# design.net
KiCad netlist of a schematic drawn in Altium Designer
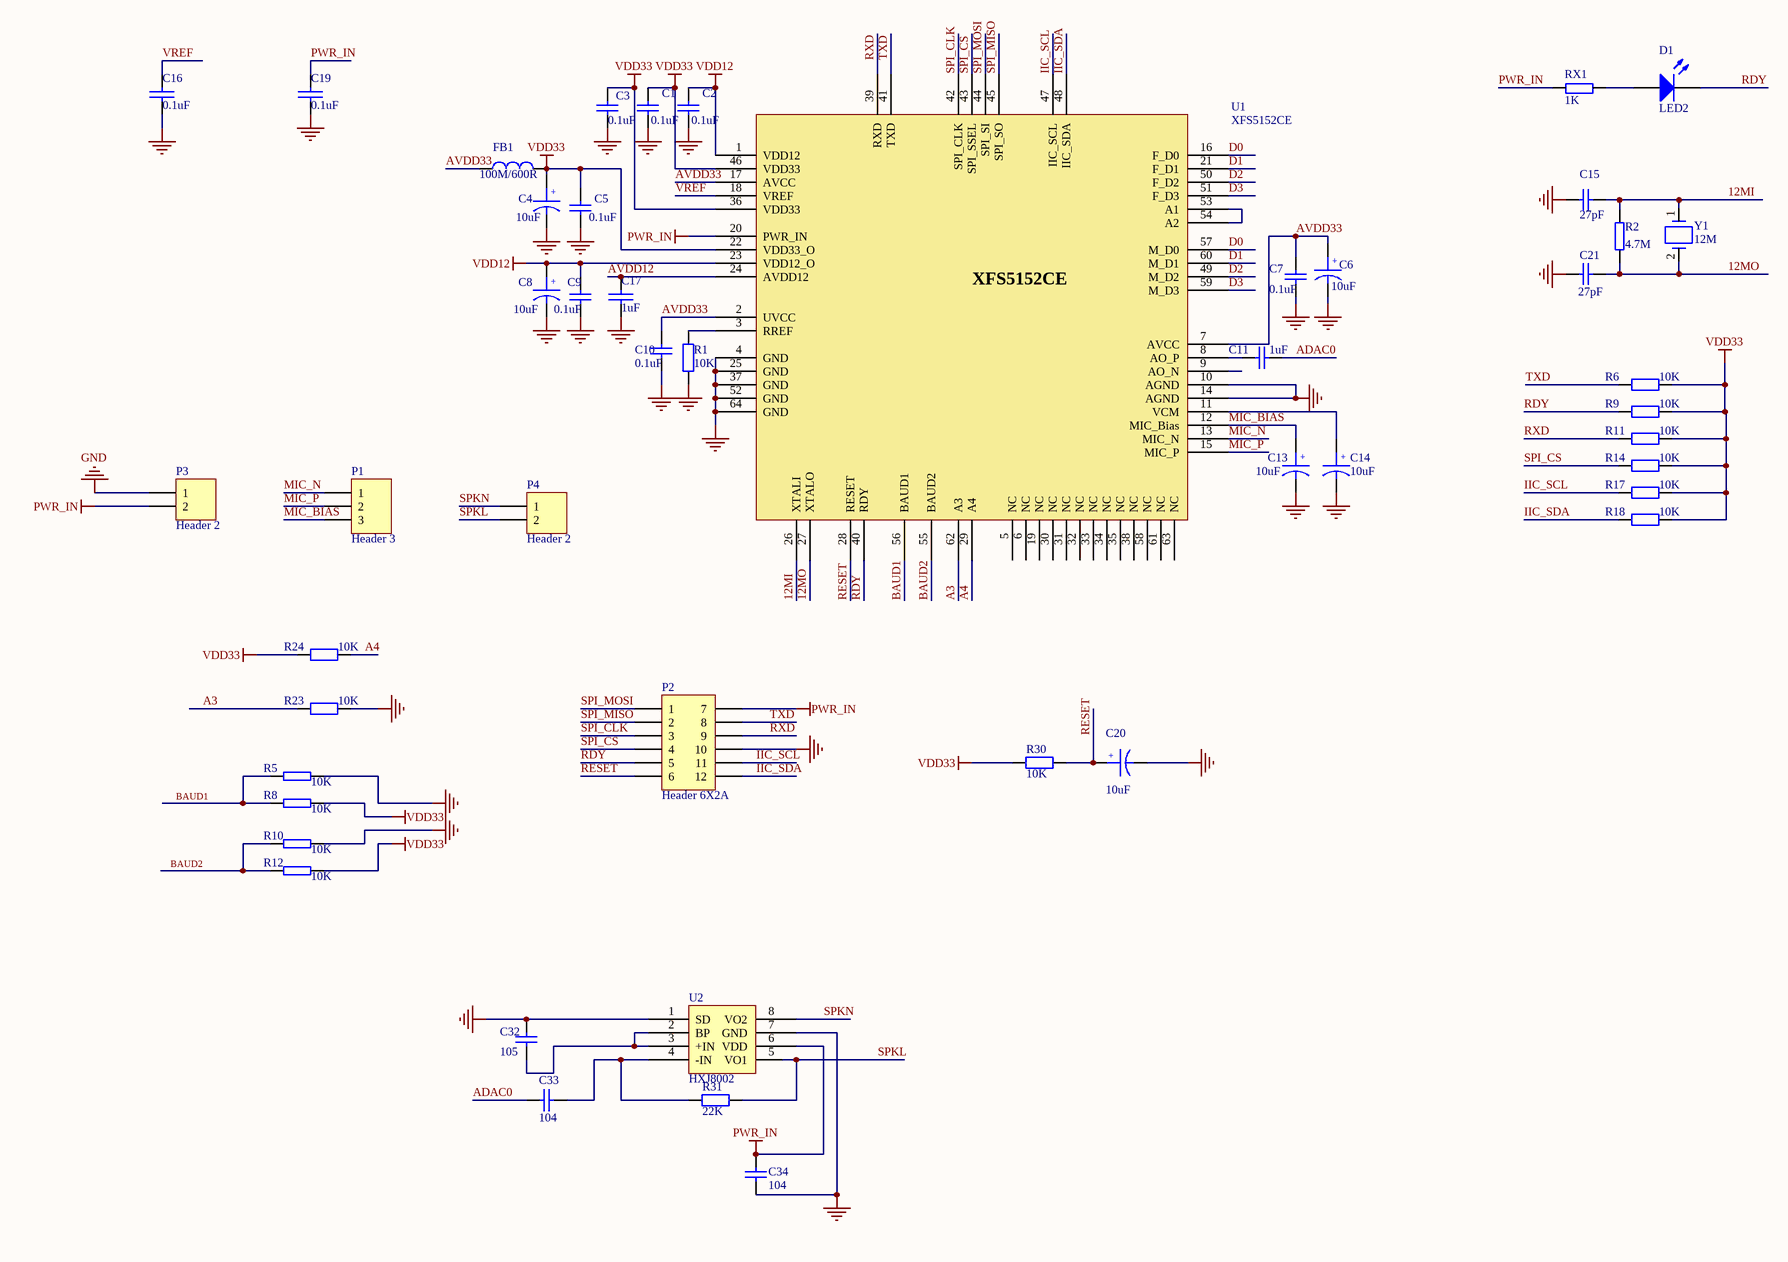
[diagram p0: 日原理图.SchDoc]

(export (version "E")
  (design (tool "Eeschema 10.0.6"))
  (components
    (comp (ref "C1")
      (value "0.1uF")
      (footprint "0603P")
      (description "电容")
      (fields (field (name "PUBLISHER") "Altium Limited"))
      (libsource (lib "*") (part "Cap NP"))
    )
    (comp (ref "C2")
      (value "0.1uF")
      (footprint "0603P")
      (description "电容")
      (fields (field (name "PUBLISHER") "Altium Limited"))
      (libsource (lib "*") (part "Cap NP"))
    )
    (comp (ref "C3")
      (value "0.1uF")
      (footprint "0603P")
      (description "电容")
      (fields (field (name "PUBLISHER") "Altium Limited"))
      (libsource (lib "*") (part "Cap NP"))
    )
    (comp (ref "C4") (value "10uF") (footprint "0805") (libsource (lib "*") (part "CAP POL")))
    (comp (ref "C5")
      (value "0.1uF")
      (footprint "0603P")
      (description "电容")
      (fields (field (name "PUBLISHER") "Altium Limited"))
      (libsource (lib "*") (part "Cap NP"))
    )
    (comp (ref "C6") (value "10uF") (footprint "0805") (libsource (lib "*") (part "CAP POL")))
    (comp (ref "C7")
      (value "0.1uF")
      (footprint "0603P")
      (description "电容")
      (fields (field (name "PUBLISHER") "Altium Limited"))
      (libsource (lib "*") (part "Cap NP"))
    )
    (comp (ref "C8") (value "10uF") (footprint "0805") (libsource (lib "*") (part "CAP POL")))
    (comp (ref "C9")
      (value "0.1uF")
      (footprint "0603P")
      (description "电容")
      (fields (field (name "PUBLISHER") "Altium Limited"))
      (libsource (lib "*") (part "Cap NP"))
    )
    (comp (ref "C10")
      (value "0.1uF")
      (footprint "0603P")
      (description "电容")
      (fields (field (name "PUBLISHER") "Altium Limited"))
      (libsource (lib "*") (part "Cap NP"))
    )
    (comp (ref "C11")
      (value "1uF")
      (footprint "0603P")
      (description "电容")
      (fields (field (name "PUBLISHER") "Altium Limited"))
      (libsource (lib "*") (part "Cap NP"))
    )
    (comp (ref "C13") (value "10uF") (footprint "0805") (libsource (lib "*") (part "CAP POL")))
    (comp (ref "C14") (value "10uF") (footprint "0805") (libsource (lib "*") (part "CAP POL")))
    (comp (ref "C15")
      (value "27pF")
      (footprint "0603P")
      (description "电容")
      (fields (field (name "PUBLISHER") "Altium Limited"))
      (libsource (lib "*") (part "Cap NP"))
    )
    (comp (ref "C16")
      (value "0.1uF")
      (footprint "0603P")
      (description "Capacitor")
      (libsource (lib "*") (part "CAP"))
    )
    (comp (ref "C17")
      (value "1uF")
      (footprint "0603P")
      (description "Capacitor")
      (libsource (lib "*") (part "CAP"))
    )
    (comp (ref "C19")
      (value "0.1uF")
      (footprint "0603P")
      (description "Capacitor")
      (libsource (lib "*") (part "CAP"))
    )
    (comp (ref "C20") (value "10uF") (footprint "0603P") (libsource (lib "*") (part "CAP POL")))
    (comp (ref "C21")
      (value "27pF")
      (footprint "0603P")
      (description "电容")
      (fields (field (name "PUBLISHER") "Altium Limited"))
      (libsource (lib "*") (part "Cap NP"))
    )
    (comp (ref "C32")
      (value "105")
      (footprint "0603P")
      (description "电容")
      (fields (field (name "PUBLISHER") "Altium Limited"))
      (libsource (lib "*") (part "Cap NP"))
    )
    (comp (ref "C33")
      (value "104")
      (footprint "0603P")
      (description "电容")
      (fields (field (name "PUBLISHER") "Altium Limited"))
      (libsource (lib "*") (part "Cap NP"))
    )
    (comp (ref "C34")
      (value "104")
      (footprint "0603P")
      (description "电容")
      (fields (field (name "PUBLISHER") "Altium Limited"))
      (libsource (lib "*") (part "Cap NP"))
    )
    (comp (ref "D1")
      (value "LED2")
      (footprint "3.2X1.6X1.1")
      (description "Typical RED, GREEN, YELLOW, AMBER GaAs LED")
      (fields (field (name "PUBLISHER") "Altium Limited"))
      (libsource (lib "Miscellaneous Devices") (part "LED2"))
    )
    (comp (ref "FB1")
      (value "100M/600R")
      (footprint "0603P")
      (description "磁珠")
      (fields (field (name "PUBLISHER") "Altium Limited"))
      (libsource (lib "*") (part "Fbead"))
    )
    (comp (ref "P1")
      (value "Header 3")
      (footprint "HDR1X3")
      (description "Header, 3-Pin")
      (fields (field (name "PUBLISHER") "Altium Limited"))
      (libsource (lib "Miscellaneous Connectors") (part "Header 3"))
    )
    (comp (ref "P2")
      (value "Header 6X2A")
      (footprint "HDR2X6_CEN")
      (description "Header, 6-Pin, Dual row")
      (fields (field (name "PUBLISHER") "Altium Limited"))
      (libsource (lib "Miscellaneous Connectors") (part "Header 6X2A"))
    )
    (comp (ref "P3")
      (value "Header 2")
      (footprint "HDR1X2")
      (description "Header, 2-Pin")
      (fields (field (name "PUBLISHER") "Altium Limited"))
      (libsource (lib "Miscellaneous Connectors") (part "Header 2"))
    )
    (comp (ref "P4")
      (value "Header 2")
      (footprint "HDR1X2")
      (description "Header, 2-Pin")
      (fields (field (name "PUBLISHER") "Altium Limited"))
      (libsource (lib "Miscellaneous Connectors") (part "Header 2"))
    )
    (comp (ref "R1")
      (value "10K")
      (footprint "0603P")
      (description "Resistor")
      (fields (field (name "PUBLISHER") "Altium Limited"))
      (libsource (lib "") (part "Res2_1"))
    )
    (comp (ref "R2")
      (value "4.7M")
      (footprint "R0603")
      (description "电阻")
      (libsource (lib "*") (part "RES2"))
    )
    (comp (ref "R5") (value "10K") (footprint "R0603") (description "电阻") (libsource (lib "*") (part "RES2")))
    (comp (ref "R6")
      (value "10K")
      (footprint "R0603")
      (description "Resistor")
      (fields (field (name "PUBLISHER") "Altium Limited"))
      (libsource (lib "*") (part "Res2"))
    )
    (comp (ref "R8") (value "10K") (footprint "R0603") (description "电阻") (libsource (lib "*") (part "RES2")))
    (comp (ref "R9")
      (value "10K")
      (footprint "R0603")
      (description "Resistor")
      (fields (field (name "PUBLISHER") "Altium Limited"))
      (libsource (lib "*") (part "Res2"))
    )
    (comp (ref "R10")
      (value "10K")
      (footprint "R0603")
      (description "电阻")
      (libsource (lib "*") (part "RES2"))
    )
    (comp (ref "R11")
      (value "10K")
      (footprint "R0603")
      (description "Resistor")
      (fields (field (name "PUBLISHER") "Altium Limited"))
      (libsource (lib "*") (part "Res2"))
    )
    (comp (ref "R12")
      (value "10K")
      (footprint "R0603")
      (description "电阻")
      (libsource (lib "*") (part "RES2"))
    )
    (comp (ref "R14")
      (value "10K")
      (footprint "R0603")
      (description "Resistor")
      (fields (field (name "PUBLISHER") "Altium Limited"))
      (libsource (lib "*") (part "Res2"))
    )
    (comp (ref "R17")
      (value "10K")
      (footprint "R0603")
      (description "Resistor")
      (fields (field (name "PUBLISHER") "Altium Limited"))
      (libsource (lib "*") (part "Res2"))
    )
    (comp (ref "R18")
      (value "10K")
      (footprint "R0603")
      (description "Resistor")
      (fields (field (name "PUBLISHER") "Altium Limited"))
      (libsource (lib "*") (part "Res2"))
    )
    (comp (ref "R23")
      (value "10K")
      (footprint "R0603")
      (description "Resistor")
      (fields (field (name "PUBLISHER") "Altium Limited"))
      (libsource (lib "*") (part "Res2"))
    )
    (comp (ref "R24")
      (value "10K")
      (footprint "R0603")
      (description "Resistor")
      (fields (field (name "PUBLISHER") "Altium Limited"))
      (libsource (lib "*") (part "Res2"))
    )
    (comp (ref "R30")
      (value "10K")
      (footprint "R0603")
      (description "Resistor")
      (fields (field (name "PUBLISHER") "Altium Limited"))
      (libsource (lib "") (part "Res2_2"))
    )
    (comp (ref "R31")
      (value "22K")
      (footprint "R0603")
      (description "Resistor")
      (fields (field (name "PUBLISHER") "Altium Limited"))
      (libsource (lib "") (part "Res2_2"))
    )
    (comp (ref "RX1") (value "1K") (footprint "0603P") (libsource (lib "EliteSTM32封装库") (part "R")))
    (comp (ref "U1") (value "XFS5152CE") (footprint "LQFP64") (libsource (lib "*") (part "XFS5152-2")))
    (comp (ref "U2") (value "HXJ8002") (footprint "SOP-8") (libsource (lib "MY libraiy") (part "HXJ8002")))
    (comp (ref "Y1")
      (value "12M")
      (footprint "XTAL_US")
      (description "晶振")
      (libsource (lib "*") (part "XTAL1"))
    )
  )
  (nets
    (net (code "1") (name "/12MI") (class "Default")
      (node (ref "C15") (pin "2") (pinfunction "2_2") (pintype "passive"))
      (node (ref "R2") (pin "1") (pintype "passive"))
      (node (ref "U1") (pin "26") (pinfunction "XTALI_26") (pintype "passive"))
      (node (ref "Y1") (pin "1") (pinfunction "1_1") (pintype "passive"))
    )
    (net (code "2") (name "/12MO") (class "Default")
      (node (ref "C21") (pin "2") (pinfunction "2_2") (pintype "passive"))
      (node (ref "R2") (pin "2") (pintype "passive"))
      (node (ref "U1") (pin "27") (pinfunction "XTALO_27") (pintype "passive"))
    )
    (net (code "3") (name "/A3") (class "Default")
      (node (ref "R23") (pin "2") (pinfunction "2_2") (pintype "passive"))
      (node (ref "U1") (pin "62") (pinfunction "A3_62") (pintype "passive"))
    )
    (net (code "4") (name "/A4") (class "Default")
      (node (ref "R24") (pin "1") (pinfunction "1_1") (pintype "passive"))
      (node (ref "U1") (pin "29") (pinfunction "A4_29") (pintype "passive"))
    )
    (net (code "5") (name "/ADAC0") (class "Default")
      (node (ref "C11") (pin "1") (pinfunction "1_1") (pintype "passive"))
      (node (ref "C33") (pin "2") (pinfunction "2_2") (pintype "passive"))
    )
    (net (code "6") (name "/AVDD12") (class "Default")
      (node (ref "C17") (pin "1") (pinfunction "1_1") (pintype "passive"))
      (node (ref "U1") (pin "24") (pinfunction "AVDD12_24") (pintype "passive"))
    )
    (net (code "7") (name "/AVDD33") (class "Default")
      (node (ref "C10") (pin "2") (pinfunction "2_2") (pintype "passive"))
      (node (ref "C6") (pin "1") (pinfunction "1_1") (pintype "passive"))
      (node (ref "C7") (pin "2") (pinfunction "2_2") (pintype "passive"))
      (node (ref "FB1") (pin "1") (pinfunction "1_1") (pintype "passive"))
      (node (ref "U1") (pin "17") (pinfunction "AVCC_17") (pintype "passive"))
      (node (ref "U1") (pin "2") (pinfunction "UVCC_2") (pintype "passive"))
      (node (ref "U1") (pin "7") (pinfunction "AVCC_7") (pintype "passive"))
    )
    (net (code "8") (name "/BAUD1") (class "Default")
      (node (ref "R5") (pin "2") (pintype "passive"))
      (node (ref "R8") (pin "2") (pintype "passive"))
      (node (ref "U1") (pin "56") (pinfunction "BAUD1_56") (pintype "passive"))
    )
    (net (code "9") (name "/BAUD2") (class "Default")
      (node (ref "R10") (pin "2") (pintype "passive"))
      (node (ref "R12") (pin "1") (pintype "passive"))
      (node (ref "U1") (pin "55") (pinfunction "BAUD2_55") (pintype "passive"))
    )
    (net (code "10") (name "/D0") (class "Default")
      (node (ref "U1") (pin "16") (pinfunction "F_D0_16") (pintype "passive"))
      (node (ref "U1") (pin "57") (pinfunction "M_D0_57") (pintype "passive"))
    )
    (net (code "11") (name "/D1") (class "Default")
      (node (ref "U1") (pin "21") (pinfunction "F_D1_21") (pintype "passive"))
      (node (ref "U1") (pin "60") (pinfunction "M_D1_60") (pintype "passive"))
    )
    (net (code "12") (name "/D2") (class "Default")
      (node (ref "U1") (pin "49") (pinfunction "M_D2_49") (pintype "passive"))
      (node (ref "U1") (pin "50") (pinfunction "F_D2_50") (pintype "passive"))
    )
    (net (code "13") (name "/D3") (class "Default")
      (node (ref "U1") (pin "51") (pinfunction "F_D3_51") (pintype "passive"))
      (node (ref "U1") (pin "59") (pinfunction "M_D3_59") (pintype "passive"))
    )
    (net (code "14") (name "/IIC_SCL") (class "Default")
      (node (ref "P2") (pin "11") (pinfunction "11_11") (pintype "passive"))
      (node (ref "R17") (pin "2") (pinfunction "2_2") (pintype "passive"))
      (node (ref "U1") (pin "47") (pinfunction "IIC_SCL_47") (pintype "passive"))
    )
    (net (code "15") (name "/IIC_SDA") (class "Default")
      (node (ref "P2") (pin "12") (pinfunction "12_12") (pintype "passive"))
      (node (ref "R18") (pin "2") (pinfunction "2_2") (pintype "passive"))
      (node (ref "U1") (pin "48") (pinfunction "IIC_SDA_48") (pintype "passive"))
    )
    (net (code "16") (name "/MIC_BIAS") (class "Default")
      (node (ref "C13") (pin "1") (pinfunction "1_1") (pintype "passive"))
      (node (ref "P1") (pin "3") (pinfunction "3_3") (pintype "passive"))
      (node (ref "U1") (pin "12") (pinfunction "MIC_Bias_12") (pintype "passive"))
    )
    (net (code "17") (name "/MIC_N") (class "Default")
      (node (ref "P1") (pin "1") (pinfunction "1_1") (pintype "passive"))
      (node (ref "U1") (pin "13") (pinfunction "MIC_N_13") (pintype "passive"))
    )
    (net (code "18") (name "/MIC_P") (class "Default")
      (node (ref "P1") (pin "2") (pinfunction "2_2") (pintype "passive"))
      (node (ref "U1") (pin "15") (pinfunction "MIC_P_15") (pintype "passive"))
    )
    (net (code "19") (name "/RDY") (class "Default")
      (node (ref "D1") (pin "2") (pinfunction "K_2") (pintype "passive"))
      (node (ref "P2") (pin "5") (pinfunction "5_5") (pintype "passive"))
      (node (ref "R9") (pin "2") (pinfunction "2_2") (pintype "passive"))
      (node (ref "U1") (pin "40") (pinfunction "RDY_40") (pintype "passive"))
    )
    (net (code "20") (name "/RESET") (class "Default")
      (node (ref "C20") (pin "1") (pinfunction "1_1") (pintype "passive"))
      (node (ref "P2") (pin "6") (pinfunction "6_6") (pintype "passive"))
      (node (ref "R30") (pin "2") (pinfunction "2_2") (pintype "passive"))
      (node (ref "U1") (pin "28") (pinfunction "RESET_28") (pintype "passive"))
    )
    (net (code "21") (name "/RXD") (class "Default")
      (node (ref "P2") (pin "9") (pinfunction "9_9") (pintype "passive"))
      (node (ref "R11") (pin "2") (pinfunction "2_2") (pintype "passive"))
      (node (ref "U1") (pin "39") (pinfunction "RXD_39") (pintype "passive"))
    )
    (net (code "22") (name "/SPI_CLK") (class "Default")
      (node (ref "P2") (pin "3") (pinfunction "3_3") (pintype "passive"))
      (node (ref "U1") (pin "42") (pinfunction "SPI_CLK_42") (pintype "passive"))
    )
    (net (code "23") (name "/SPI_CS") (class "Default")
      (node (ref "P2") (pin "4") (pinfunction "4_4") (pintype "passive"))
      (node (ref "R14") (pin "2") (pinfunction "2_2") (pintype "passive"))
      (node (ref "U1") (pin "43") (pinfunction "SPI_SSEL_43") (pintype "passive"))
    )
    (net (code "24") (name "/SPI_MISO") (class "Default")
      (node (ref "P2") (pin "2") (pinfunction "2_2") (pintype "passive"))
      (node (ref "U1") (pin "45") (pinfunction "SPI_SO_45") (pintype "passive"))
    )
    (net (code "25") (name "/SPI_MOSI") (class "Default")
      (node (ref "P2") (pin "1") (pinfunction "1_1") (pintype "passive"))
      (node (ref "U1") (pin "44") (pinfunction "SPI_SI_44") (pintype "passive"))
    )
    (net (code "26") (name "/SPKL") (class "Default")
      (node (ref "P4") (pin "2") (pinfunction "2_2") (pintype "passive"))
      (node (ref "R31") (pin "2") (pinfunction "2_2") (pintype "passive"))
      (node (ref "U2") (pin "5") (pinfunction "VO1_5") (pintype "passive"))
    )
    (net (code "27") (name "/SPKN") (class "Default")
      (node (ref "P4") (pin "1") (pinfunction "1_1") (pintype "passive"))
      (node (ref "U2") (pin "8") (pinfunction "VO2_8") (pintype "passive"))
    )
    (net (code "28") (name "/TXD") (class "Default")
      (node (ref "P2") (pin "8") (pinfunction "8_8") (pintype "passive"))
      (node (ref "R6") (pin "2") (pinfunction "2_2") (pintype "passive"))
      (node (ref "U1") (pin "41") (pinfunction "TXD_41") (pintype "passive"))
    )
    (net (code "29") (name "/VREF") (class "Default")
      (node (ref "C16") (pin "1") (pinfunction "1_1") (pintype "passive"))
      (node (ref "U1") (pin "18") (pinfunction "VREF_18") (pintype "passive"))
    )
    (net (code "30") (name "GND") (class "Default")
      (node (ref "C1") (pin "1") (pinfunction "1_1") (pintype "passive"))
      (node (ref "C10") (pin "1") (pinfunction "1_1") (pintype "passive"))
      (node (ref "C13") (pin "2") (pinfunction "2_2") (pintype "passive"))
      (node (ref "C14") (pin "2") (pinfunction "2_2") (pintype "passive"))
      (node (ref "C15") (pin "1") (pinfunction "1_1") (pintype "passive"))
      (node (ref "C16") (pin "2") (pinfunction "2_2") (pintype "passive"))
      (node (ref "C17") (pin "2") (pinfunction "2_2") (pintype "passive"))
      (node (ref "C19") (pin "2") (pinfunction "2_2") (pintype "passive"))
      (node (ref "C2") (pin "1") (pinfunction "1_1") (pintype "passive"))
      (node (ref "C20") (pin "2") (pinfunction "2_2") (pintype "passive"))
      (node (ref "C21") (pin "1") (pinfunction "1_1") (pintype "passive"))
      (node (ref "C3") (pin "1") (pinfunction "1_1") (pintype "passive"))
      (node (ref "C32") (pin "2") (pinfunction "2_2") (pintype "passive"))
      (node (ref "C34") (pin "2") (pinfunction "2_2") (pintype "passive"))
      (node (ref "C4") (pin "2") (pinfunction "2_2") (pintype "passive"))
      (node (ref "C5") (pin "1") (pinfunction "1_1") (pintype "passive"))
      (node (ref "C6") (pin "2") (pinfunction "2_2") (pintype "passive"))
      (node (ref "C7") (pin "1") (pinfunction "1_1") (pintype "passive"))
      (node (ref "C8") (pin "2") (pinfunction "2_2") (pintype "passive"))
      (node (ref "C9") (pin "1") (pinfunction "1_1") (pintype "passive"))
      (node (ref "P2") (pin "10") (pinfunction "10_10") (pintype "passive"))
      (node (ref "P3") (pin "1") (pinfunction "1_1") (pintype "passive"))
      (node (ref "R1") (pin "1") (pinfunction "1_1") (pintype "passive"))
      (node (ref "R10") (pin "1") (pintype "passive"))
      (node (ref "R23") (pin "1") (pinfunction "1_1") (pintype "passive"))
      (node (ref "R5") (pin "1") (pintype "passive"))
      (node (ref "U1") (pin "10") (pinfunction "AGND_10") (pintype "passive"))
      (node (ref "U1") (pin "14") (pinfunction "AGND_14") (pintype "passive"))
      (node (ref "U1") (pin "25") (pinfunction "GND_25") (pintype "passive"))
      (node (ref "U1") (pin "37") (pinfunction "GND_37") (pintype "passive"))
      (node (ref "U1") (pin "4") (pinfunction "GND_4") (pintype "passive"))
      (node (ref "U1") (pin "52") (pinfunction "GND_52") (pintype "passive"))
      (node (ref "U1") (pin "64") (pinfunction "GND_64") (pintype "passive"))
      (node (ref "U2") (pin "1") (pinfunction "SD_1") (pintype "passive"))
      (node (ref "U2") (pin "7") (pinfunction "GND_7") (pintype "passive"))
    )
    (net (code "31") (name "Net-(D1-A)") (class "Default")
      (node (ref "D1") (pin "1") (pinfunction "A_1") (pintype "passive"))
      (node (ref "RX1") (pin "2") (pintype "passive"))
    )
    (net (code "32") (name "Net-(U1-A1)") (class "Default")
      (node (ref "U1") (pin "53") (pinfunction "A1_53") (pintype "passive"))
      (node (ref "U1") (pin "54") (pinfunction "A2_54") (pintype "passive"))
    )
    (net (code "33") (name "Net-(U1-AO_P)") (class "Default")
      (node (ref "C11") (pin "2") (pinfunction "2_2") (pintype "passive"))
      (node (ref "U1") (pin "8") (pinfunction "AO_P_8") (pintype "passive"))
    )
    (net (code "34") (name "Net-(U1-RREF)") (class "Default")
      (node (ref "R1") (pin "2") (pinfunction "2_2") (pintype "passive"))
      (node (ref "U1") (pin "3") (pinfunction "RREF_3") (pintype "passive"))
    )
    (net (code "35") (name "Net-(U1-VCM)") (class "Default")
      (node (ref "C14") (pin "1") (pinfunction "1_1") (pintype "passive"))
      (node (ref "U1") (pin "11") (pinfunction "VCM_11") (pintype "passive"))
    )
    (net (code "36") (name "Net-(U2-+IN)") (class "Default")
      (node (ref "C32") (pin "1") (pinfunction "1_1") (pintype "passive"))
      (node (ref "U2") (pin "2") (pinfunction "BP_2") (pintype "passive"))
      (node (ref "U2") (pin "3") (pinfunction "+IN_3") (pintype "passive"))
    )
    (net (code "37") (name "Net-(U2--IN)") (class "Default")
      (node (ref "C33") (pin "1") (pinfunction "1_1") (pintype "passive"))
      (node (ref "R31") (pin "1") (pinfunction "1_1") (pintype "passive"))
      (node (ref "U2") (pin "4") (pinfunction "-IN_4") (pintype "passive"))
    )
    (net (code "38") (name "PWR_IN") (class "Default")
      (node (ref "C19") (pin "1") (pinfunction "1_1") (pintype "passive"))
      (node (ref "C34") (pin "1") (pinfunction "1_1") (pintype "passive"))
      (node (ref "P2") (pin "7") (pinfunction "7_7") (pintype "passive"))
      (node (ref "P3") (pin "2") (pinfunction "2_2") (pintype "passive"))
      (node (ref "RX1") (pin "1") (pintype "passive"))
      (node (ref "U1") (pin "20") (pinfunction "PWR_IN_20") (pintype "passive"))
      (node (ref "U2") (pin "6") (pinfunction "VDD_6") (pintype "passive"))
    )
    (net (code "39") (name "VDD12") (class "Default")
      (node (ref "C2") (pin "2") (pinfunction "2_2") (pintype "passive"))
      (node (ref "C8") (pin "1") (pinfunction "1_1") (pintype "passive"))
      (node (ref "C9") (pin "2") (pinfunction "2_2") (pintype "passive"))
      (node (ref "U1") (pin "1") (pinfunction "VDD12_1") (pintype "passive"))
      (node (ref "U1") (pin "23") (pinfunction "VDD12_O_23") (pintype "passive"))
    )
    (net (code "40") (name "VDD33") (class "Default")
      (node (ref "C1") (pin "2") (pinfunction "2_2") (pintype "passive"))
      (node (ref "C3") (pin "2") (pinfunction "2_2") (pintype "passive"))
      (node (ref "C4") (pin "1") (pinfunction "1_1") (pintype "passive"))
      (node (ref "C5") (pin "2") (pinfunction "2_2") (pintype "passive"))
      (node (ref "FB1") (pin "2") (pinfunction "2_2") (pintype "passive"))
      (node (ref "R11") (pin "1") (pinfunction "1_1") (pintype "passive"))
      (node (ref "R12") (pin "2") (pintype "passive"))
      (node (ref "R14") (pin "1") (pinfunction "1_1") (pintype "passive"))
      (node (ref "R17") (pin "1") (pinfunction "1_1") (pintype "passive"))
      (node (ref "R18") (pin "1") (pinfunction "1_1") (pintype "passive"))
      (node (ref "R24") (pin "2") (pinfunction "2_2") (pintype "passive"))
      (node (ref "R30") (pin "1") (pinfunction "1_1") (pintype "passive"))
      (node (ref "R6") (pin "1") (pinfunction "1_1") (pintype "passive"))
      (node (ref "R8") (pin "1") (pintype "passive"))
      (node (ref "R9") (pin "1") (pinfunction "1_1") (pintype "passive"))
      (node (ref "U1") (pin "22") (pinfunction "VDD33_O_22") (pintype "passive"))
      (node (ref "U1") (pin "36") (pinfunction "VDD33_36") (pintype "passive"))
      (node (ref "U1") (pin "46") (pinfunction "VDD33_46") (pintype "passive"))
    )
    (net (code "41") (name "unconnected-(U1-AO_N-Pad9)") (class "Default")
      (node (ref "U1") (pin "9") (pinfunction "AO_N_9") (pintype "passive"))
    )
    (net (code "42") (name "unconnected-(U1-NC-Pad5)") (class "Default")
      (node (ref "U1") (pin "5") (pinfunction "NC_5") (pintype "passive"))
    )
    (net (code "43") (name "unconnected-(U1-NC-Pad6)") (class "Default")
      (node (ref "U1") (pin "6") (pinfunction "NC_6") (pintype "passive"))
    )
    (net (code "44") (name "unconnected-(U1-NC-Pad19)") (class "Default")
      (node (ref "U1") (pin "19") (pinfunction "NC_19") (pintype "passive"))
    )
    (net (code "45") (name "unconnected-(U1-NC-Pad30)") (class "Default")
      (node (ref "U1") (pin "30") (pinfunction "NC_30") (pintype "passive"))
    )
    (net (code "46") (name "unconnected-(U1-NC-Pad31)") (class "Default")
      (node (ref "U1") (pin "31") (pinfunction "NC_31") (pintype "passive"))
    )
    (net (code "47") (name "unconnected-(U1-NC-Pad32)") (class "Default")
      (node (ref "U1") (pin "32") (pinfunction "NC_32") (pintype "passive"))
    )
    (net (code "48") (name "unconnected-(U1-NC-Pad33)") (class "Default")
      (node (ref "U1") (pin "33") (pinfunction "NC_33") (pintype "passive"))
    )
    (net (code "49") (name "unconnected-(U1-NC-Pad34)") (class "Default")
      (node (ref "U1") (pin "34") (pinfunction "NC_34") (pintype "passive"))
    )
    (net (code "50") (name "unconnected-(U1-NC-Pad35)") (class "Default")
      (node (ref "U1") (pin "35") (pinfunction "NC_35") (pintype "passive"))
    )
    (net (code "51") (name "unconnected-(U1-NC-Pad38)") (class "Default")
      (node (ref "U1") (pin "38") (pinfunction "NC_38") (pintype "passive"))
    )
    (net (code "52") (name "unconnected-(U1-NC-Pad58)") (class "Default")
      (node (ref "U1") (pin "58") (pinfunction "NC_58") (pintype "passive"))
    )
    (net (code "53") (name "unconnected-(U1-NC-Pad61)") (class "Default")
      (node (ref "U1") (pin "61") (pinfunction "NC_61") (pintype "passive"))
    )
    (net (code "54") (name "unconnected-(U1-NC-Pad63)") (class "Default")
      (node (ref "U1") (pin "63") (pinfunction "NC_63") (pintype "passive"))
    )
    (net (code "55") (name "unconnected-(Y1-Pad2)") (class "Default")
      (node (ref "Y1") (pin "2") (pinfunction "2_2") (pintype "passive"))
    )
  )
)
